# AMU-S04-V00-Microcontroller.net
KiCad netlist of a schematic drawn in Altium Designer
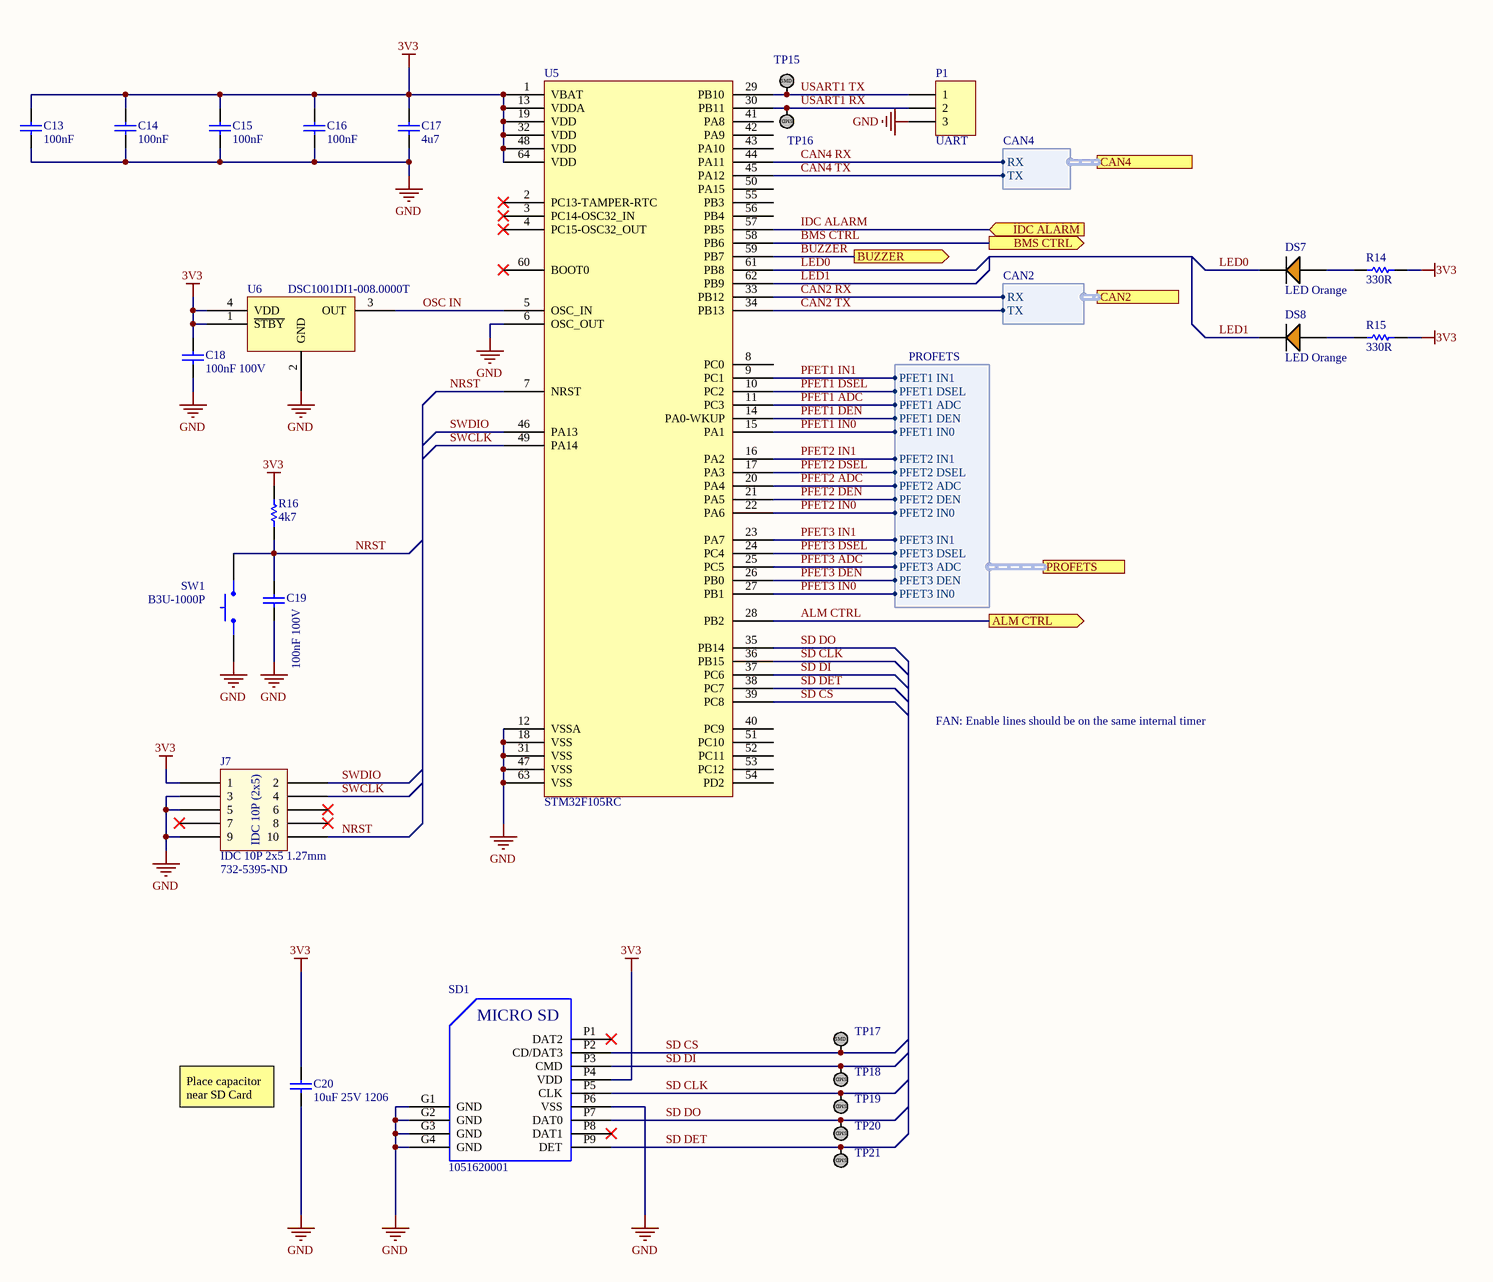
[diagram p0: AMU-S04-V00-Microcontroller.SchDoc]

(export (version "E")
  (design (tool "Eeschema 10.0.6"))
  (components
    (comp (ref "C13")
      (value "100nF")
      (footprint "Cap_Ceramic_0603")
      (description "Capacitor, Ceramic, SMD, 100nF, 50V, 5%, X7R, 0603")
      (libsource (lib "StandardCapacitors") (part "100nF 50V 5% X7R 0603"))
    )
    (comp (ref "C14")
      (value "100nF")
      (footprint "Cap_Ceramic_0603")
      (description "Capacitor, Ceramic, SMD, 100nF, 50V, 5%, X7R, 0603")
      (libsource (lib "StandardCapacitors") (part "100nF 50V 5% X7R 0603"))
    )
    (comp (ref "C15")
      (value "100nF")
      (footprint "Cap_Ceramic_0603")
      (description "Capacitor, Ceramic, SMD, 100nF, 50V, 5%, X7R, 0603")
      (libsource (lib "StandardCapacitors") (part "100nF 50V 5% X7R 0603"))
    )
    (comp (ref "C16")
      (value "100nF")
      (footprint "Cap_Ceramic_0603")
      (description "Capacitor, Ceramic, SMD, 100nF, 50V, 5%, X7R, 0603")
      (libsource (lib "StandardCapacitors") (part "100nF 50V 5% X7R 0603"))
    )
    (comp (ref "C17")
      (value "4u7")
      (footprint "Cap_Ceramic_0603")
      (description "Capacitor, Ceramic, SMD, 4u7, 50V, 5%, X7R, 0603")
      (libsource (lib "StandardCapacitors") (part "4u7 50V 5% X7R 0603"))
    )
    (comp (ref "C18")
      (value "100nF 100V")
      (footprint "Cap_Ceramic_0603")
      (description "Capacitor, Ceramic, SMD, 100nF, 100V, 5%, X7R, 0603")
      (libsource (lib "StandardCapacitors") (part "100nF 100V 5% X7R 0603"))
    )
    (comp (ref "C19")
      (value "100nF 100V")
      (footprint "Cap_Ceramic_0603")
      (description "Capacitor, Ceramic, SMD, 100nF, 100V, 5%, X7R, 0603")
      (libsource (lib "StandardCapacitors") (part "100nF 100V 5% X7R 0603"))
    )
    (comp (ref "C20")
      (value "10uF 25V 1206")
      (footprint "Cap_Ceramic_1206")
      (description "Capacitor, Ceramic, SMD, 10uF, 25V, 10%, X7R, 1206")
      (libsource (lib "StandardCapacitors") (part "10uF 25V 10% X7R 1206"))
    )
    (comp (ref "DS7")
      (value "LED Orange")
      (footprint "LED ORANGE 0603")
      (libsource (lib "QUTMS_LEDLibrary") (part "LED ORANGE 0603"))
    )
    (comp (ref "DS8")
      (value "LED Orange")
      (footprint "LED ORANGE 0603")
      (libsource (lib "QUTMS_LEDLibrary") (part "LED ORANGE 0603"))
    )
    (comp (ref "J7")
      (value "IDC 10P 2x5 1.27mm")
      (footprint "IDC 1.27MM 10P")
      (libsource (lib "IDCConnectors") (part "IDC 10P 2x5 1.27mm"))
    )
    (comp (ref "P1")
      (value "UART")
      (footprint "HDR1X3")
      (description "Header, 3-Pin")
      (fields (field (name "PUBLISHER") "Altium Limited"))
      (libsource (lib "Miscellaneous Connectors") (part "Header 3"))
    )
    (comp (ref "R14")
      (value "330R")
      (footprint "Res_ThinFilm_0603")
      (description "Resistor, SMD, 330R, 0.1W, 5%, 0603")
      (libsource (lib "StandardResistors") (part "330R 5% 0603"))
    )
    (comp (ref "R15")
      (value "330R")
      (footprint "Res_ThinFilm_0603")
      (description "Resistor, SMD, 330R, 0.1W, 5%, 0603")
      (libsource (lib "StandardResistors") (part "330R 5% 0603"))
    )
    (comp (ref "R16")
      (value "4k7")
      (footprint "Res_ThinFilm_0603")
      (description "Resistor, SMD, 4k7, 0.1W, 5%, 0603")
      (libsource (lib "StandardResistors") (part "4k7 5% 0603"))
    )
    (comp (ref "SD1")
      (value "1051620001")
      (footprint "1051620001")
      (description "9 (8 + 1) Position Card Connector microSD™ Surface Mount, Right Angle Gold")
      (libsource (lib "QUTMS_SDLibrary") (part "1051620001"))
    )
    (comp (ref "SW1")
      (value "B3U-1000P")
      (footprint "BTN B3U-1000P")
      (description "Omron B3U-1000P Ultra Miniture Switch")
      (libsource (lib "QUTMS_SwitchLibrary") (part "BTN B3U-1000P"))
    )
    (comp (ref "TP15")
      (value "TestPoint_SMD")
      (footprint "TestPointSMD")
      (libsource (lib "StandardTest") (part "TestPoint_SMD"))
    )
    (comp (ref "TP16")
      (value "TestPoint_SMD")
      (footprint "TestPointSMD")
      (libsource (lib "StandardTest") (part "TestPoint_SMD"))
    )
    (comp (ref "TP17")
      (value "TestPoint_SMD")
      (footprint "TestPointSMD")
      (libsource (lib "StandardTest") (part "TestPoint_SMD"))
    )
    (comp (ref "TP18")
      (value "TestPoint_SMD")
      (footprint "TestPointSMD")
      (libsource (lib "StandardTest") (part "TestPoint_SMD"))
    )
    (comp (ref "TP19")
      (value "TestPoint_SMD")
      (footprint "TestPointSMD")
      (libsource (lib "StandardTest") (part "TestPoint_SMD"))
    )
    (comp (ref "TP20")
      (value "TestPoint_SMD")
      (footprint "TestPointSMD")
      (libsource (lib "StandardTest") (part "TestPoint_SMD"))
    )
    (comp (ref "TP21")
      (value "TestPoint_SMD")
      (footprint "TestPointSMD")
      (libsource (lib "StandardTest") (part "TestPoint_SMD"))
    )
    (comp (ref "U5")
      (value "STM32F105RC")
      (footprint "STM32F105RC")
      (description "ARM® Cortex®-M3 STM32F1 Microcontroller IC 32-Bit 72MHz 256KB (256K x 8) FLASH 64-LQFP (10x10)")
      (libsource (lib "QUTMS_STM32Library") (part "STM32F105RC"))
    )
    (comp (ref "U6")
      (value "DSC1001DI1-008.0000T")
      (footprint "DSC1001DI1-008.0000TCT-ND")
      (description "on 8MHz XO (Standard) CMOS Oscillator 1.8 ~ 3.3V Standby (Power Down) 4-SMD, No Lead")
      (libsource (lib "QUTMS_CrystalLibrary") (part "DSC1001DI1-008.0000T"))
    )
  )
  (nets
    (net (code "4") (name "/ALM CTRL") (class "Default")
      (node (ref "U5") (pin "28") (pinfunction "PB2_28") (pintype "passive"))
    )
    (net (code "5") (name "/BMS CTRL") (class "Default")
      (node (ref "U5") (pin "58") (pinfunction "PB6_58") (pintype "passive"))
    )
    (net (code "6") (name "/BUZZER") (class "Default")
      (node (ref "U5") (pin "59") (pinfunction "PB7_59") (pintype "passive"))
    )
    (net (code "7") (name "/CAN2 RX") (class "Default")
      (node (ref "U5") (pin "33") (pinfunction "PB12_33") (pintype "passive"))
    )
    (net (code "8") (name "/CAN2 TX") (class "Default")
      (node (ref "U5") (pin "34") (pinfunction "PB13_34") (pintype "passive"))
    )
    (net (code "9") (name "/CAN4 RX") (class "Default")
      (node (ref "U5") (pin "44") (pinfunction "PA11_44") (pintype "passive"))
    )
    (net (code "10") (name "/CAN4 TX") (class "Default")
      (node (ref "U5") (pin "45") (pinfunction "PA12_45") (pintype "passive"))
    )
    (net (code "11") (name "/IDC ALARM") (class "Default")
      (node (ref "U5") (pin "57") (pinfunction "PB5_57") (pintype "passive"))
    )
    (net (code "12") (name "/LED0") (class "Default")
      (node (ref "DS7") (pin "2") (pinfunction "C_2") (pintype "passive"))
      (node (ref "U5") (pin "61") (pinfunction "PB8_61") (pintype "passive"))
    )
    (net (code "13") (name "/LED1") (class "Default")
      (node (ref "DS8") (pin "2") (pinfunction "C_2") (pintype "passive"))
      (node (ref "U5") (pin "62") (pinfunction "PB9_62") (pintype "passive"))
    )
    (net (code "14") (name "/NRST") (class "Default")
      (node (ref "C19") (pin "2") (pinfunction "2_2") (pintype "passive"))
      (node (ref "J7") (pin "10") (pinfunction "10_10") (pintype "passive"))
      (node (ref "R16") (pin "1") (pinfunction "1_1") (pintype "passive"))
      (node (ref "SW1") (pin "2") (pinfunction "2_2") (pintype "passive"))
      (node (ref "U5") (pin "7") (pinfunction "NRST_7") (pintype "passive"))
    )
    (net (code "15") (name "/OSC IN") (class "Default")
      (node (ref "U5") (pin "5") (pinfunction "OSC_IN_5") (pintype "passive"))
      (node (ref "U6") (pin "3") (pinfunction "OUT_3") (pintype "passive"))
    )
    (net (code "16") (name "/PFET1 ADC") (class "Default")
      (node (ref "U5") (pin "11") (pinfunction "PC3_11") (pintype "passive"))
    )
    (net (code "17") (name "/PFET1 DEN") (class "Default")
      (node (ref "U5") (pin "14") (pinfunction "PA0-WKUP_14") (pintype "passive"))
    )
    (net (code "18") (name "/PFET1 DSEL") (class "Default")
      (node (ref "U5") (pin "10") (pinfunction "PC2_10") (pintype "passive"))
    )
    (net (code "19") (name "/PFET1 IN0") (class "Default")
      (node (ref "U5") (pin "15") (pinfunction "PA1_15") (pintype "passive"))
    )
    (net (code "20") (name "/PFET1 IN1") (class "Default")
      (node (ref "U5") (pin "9") (pinfunction "PC1_9") (pintype "passive"))
    )
    (net (code "21") (name "/PFET2 ADC") (class "Default")
      (node (ref "U5") (pin "20") (pinfunction "PA4_20") (pintype "passive"))
    )
    (net (code "22") (name "/PFET2 DEN") (class "Default")
      (node (ref "U5") (pin "21") (pinfunction "PA5_21") (pintype "passive"))
    )
    (net (code "23") (name "/PFET2 DSEL") (class "Default")
      (node (ref "U5") (pin "17") (pinfunction "PA3_17") (pintype "passive"))
    )
    (net (code "24") (name "/PFET2 IN0") (class "Default")
      (node (ref "U5") (pin "22") (pinfunction "PA6_22") (pintype "passive"))
    )
    (net (code "25") (name "/PFET2 IN1") (class "Default")
      (node (ref "U5") (pin "16") (pinfunction "PA2_16") (pintype "passive"))
    )
    (net (code "26") (name "/PFET3 ADC") (class "Default")
      (node (ref "U5") (pin "25") (pinfunction "PC5_25") (pintype "passive"))
    )
    (net (code "27") (name "/PFET3 DEN") (class "Default")
      (node (ref "U5") (pin "26") (pinfunction "PB0_26") (pintype "passive"))
    )
    (net (code "28") (name "/PFET3 DSEL") (class "Default")
      (node (ref "U5") (pin "24") (pinfunction "PC4_24") (pintype "passive"))
    )
    (net (code "29") (name "/PFET3 IN0") (class "Default")
      (node (ref "U5") (pin "27") (pinfunction "PB1_27") (pintype "passive"))
    )
    (net (code "30") (name "/PFET3 IN1") (class "Default")
      (node (ref "U5") (pin "23") (pinfunction "PA7_23") (pintype "passive"))
    )
    (net (code "31") (name "/SD CLK") (class "Default")
      (node (ref "SD1") (pin "P5") (pinfunction "CLK_P5") (pintype "passive"))
      (node (ref "TP19") (pin "1") (pinfunction "1_1") (pintype "passive"))
      (node (ref "U5") (pin "36") (pinfunction "PB15_36") (pintype "passive"))
    )
    (net (code "32") (name "/SD CS") (class "Default")
      (node (ref "SD1") (pin "P2") (pinfunction "CD/DAT3_P2") (pintype "passive"))
      (node (ref "TP17") (pin "1") (pinfunction "1_1") (pintype "passive"))
      (node (ref "U5") (pin "39") (pinfunction "PC8_39") (pintype "passive"))
    )
    (net (code "33") (name "/SD DET") (class "Default")
      (node (ref "SD1") (pin "P9") (pinfunction "DET_P9") (pintype "passive"))
      (node (ref "TP21") (pin "1") (pinfunction "1_1") (pintype "passive"))
      (node (ref "U5") (pin "38") (pinfunction "PC7_38") (pintype "passive"))
    )
    (net (code "34") (name "/SD DI") (class "Default")
      (node (ref "SD1") (pin "P3") (pinfunction "CMD_P3") (pintype "passive"))
      (node (ref "TP18") (pin "1") (pinfunction "1_1") (pintype "passive"))
      (node (ref "U5") (pin "37") (pinfunction "PC6_37") (pintype "passive"))
    )
    (net (code "35") (name "/SD DO") (class "Default")
      (node (ref "SD1") (pin "P7") (pinfunction "DAT0_P7") (pintype "passive"))
      (node (ref "TP20") (pin "1") (pinfunction "1_1") (pintype "passive"))
      (node (ref "U5") (pin "35") (pinfunction "PB14_35") (pintype "passive"))
    )
    (net (code "36") (name "/SWCLK") (class "Default")
      (node (ref "J7") (pin "4") (pinfunction "4_4") (pintype "passive"))
      (node (ref "U5") (pin "49") (pinfunction "PA14_49") (pintype "passive"))
    )
    (net (code "37") (name "/SWDIO") (class "Default")
      (node (ref "J7") (pin "2") (pinfunction "2_2") (pintype "passive"))
      (node (ref "U5") (pin "46") (pinfunction "PA13_46") (pintype "passive"))
    )
    (net (code "38") (name "/USART1 RX") (class "Default")
      (node (ref "P1") (pin "2") (pinfunction "2_2") (pintype "passive"))
      (node (ref "TP16") (pin "1") (pinfunction "1_1") (pintype "passive"))
      (node (ref "U5") (pin "30") (pinfunction "PB11_30") (pintype "passive"))
    )
    (net (code "39") (name "/USART1 TX") (class "Default")
      (node (ref "P1") (pin "1") (pinfunction "1_1") (pintype "passive"))
      (node (ref "TP15") (pin "1") (pinfunction "1_1") (pintype "passive"))
      (node (ref "U5") (pin "29") (pinfunction "PB10_29") (pintype "passive"))
    )
    (net (code "43") (name "3V3") (class "Default")
      (node (ref "C13") (pin "2") (pinfunction "2_2") (pintype "passive"))
      (node (ref "C14") (pin "2") (pinfunction "2_2") (pintype "passive"))
      (node (ref "C15") (pin "2") (pinfunction "2_2") (pintype "passive"))
      (node (ref "C16") (pin "2") (pinfunction "2_2") (pintype "passive"))
      (node (ref "C17") (pin "2") (pinfunction "2_2") (pintype "passive"))
      (node (ref "C18") (pin "2") (pinfunction "2_2") (pintype "passive"))
      (node (ref "C20") (pin "2") (pinfunction "2_2") (pintype "passive"))
      (node (ref "J7") (pin "1") (pinfunction "1_1") (pintype "passive"))
      (node (ref "R14") (pin "2") (pinfunction "2_2") (pintype "passive"))
      (node (ref "R15") (pin "2") (pinfunction "2_2") (pintype "passive"))
      (node (ref "R16") (pin "2") (pinfunction "2_2") (pintype "passive"))
      (node (ref "SD1") (pin "P4") (pinfunction "VDD_P4") (pintype "passive"))
      (node (ref "U5") (pin "1") (pinfunction "VBAT_1") (pintype "passive"))
      (node (ref "U5") (pin "13") (pinfunction "VDDA_13") (pintype "passive"))
      (node (ref "U5") (pin "19") (pinfunction "VDD_19") (pintype "passive"))
      (node (ref "U5") (pin "32") (pinfunction "VDD_32") (pintype "passive"))
      (node (ref "U5") (pin "48") (pinfunction "VDD_48") (pintype "passive"))
      (node (ref "U5") (pin "64") (pinfunction "VDD_64") (pintype "passive"))
      (node (ref "U6") (pin "1") (pinfunction "~{STBY}_1") (pintype "passive"))
      (node (ref "U6") (pin "4") (pinfunction "VDD_4") (pintype "passive"))
    )
    (net (code "44") (name "GND") (class "Default")
      (node (ref "C13") (pin "1") (pinfunction "1_1") (pintype "passive"))
      (node (ref "C14") (pin "1") (pinfunction "1_1") (pintype "passive"))
      (node (ref "C15") (pin "1") (pinfunction "1_1") (pintype "passive"))
      (node (ref "C16") (pin "1") (pinfunction "1_1") (pintype "passive"))
      (node (ref "C17") (pin "1") (pinfunction "1_1") (pintype "passive"))
      (node (ref "C18") (pin "1") (pinfunction "1_1") (pintype "passive"))
      (node (ref "C19") (pin "1") (pinfunction "1_1") (pintype "passive"))
      (node (ref "C20") (pin "1") (pinfunction "1_1") (pintype "passive"))
      (node (ref "J7") (pin "3") (pinfunction "3_3") (pintype "passive"))
      (node (ref "J7") (pin "5") (pinfunction "5_5") (pintype "passive"))
      (node (ref "J7") (pin "9") (pinfunction "9_9") (pintype "passive"))
      (node (ref "P1") (pin "3") (pinfunction "3_3") (pintype "passive"))
      (node (ref "SD1") (pin "G1") (pinfunction "GND_G1") (pintype "passive"))
      (node (ref "SD1") (pin "G2") (pinfunction "GND_G2") (pintype "passive"))
      (node (ref "SD1") (pin "G3") (pinfunction "GND_G3") (pintype "passive"))
      (node (ref "SD1") (pin "G4") (pinfunction "GND_G4") (pintype "passive"))
      (node (ref "SD1") (pin "P6") (pinfunction "VSS_P6") (pintype "passive"))
      (node (ref "SW1") (pin "1") (pinfunction "1_1") (pintype "passive"))
      (node (ref "U5") (pin "12") (pinfunction "VSSA_12") (pintype "passive"))
      (node (ref "U5") (pin "18") (pinfunction "VSS_18") (pintype "passive"))
      (node (ref "U5") (pin "31") (pinfunction "VSS_31") (pintype "passive"))
      (node (ref "U5") (pin "47") (pinfunction "VSS_47") (pintype "passive"))
      (node (ref "U5") (pin "6") (pinfunction "OSC_OUT_6") (pintype "passive"))
      (node (ref "U5") (pin "63") (pinfunction "VSS_63") (pintype "passive"))
      (node (ref "U6") (pin "2") (pinfunction "GND_2") (pintype "passive"))
    )
    (net (code "45") (name "Net-(DS7-A)") (class "Default")
      (node (ref "DS7") (pin "1") (pinfunction "A_1") (pintype "passive"))
      (node (ref "R14") (pin "1") (pinfunction "1_1") (pintype "passive"))
    )
    (net (code "46") (name "Net-(DS8-A)") (class "Default")
      (node (ref "DS8") (pin "1") (pinfunction "A_1") (pintype "passive"))
      (node (ref "R15") (pin "1") (pinfunction "1_1") (pintype "passive"))
    )
    (net (code "47") (name "unconnected-(J7-Pad6)") (class "Default")
      (node (ref "J7") (pin "6") (pinfunction "6_6") (pintype "passive+no_connect"))
    )
    (net (code "48") (name "unconnected-(J7-Pad7)") (class "Default")
      (node (ref "J7") (pin "7") (pinfunction "7_7") (pintype "passive+no_connect"))
    )
    (net (code "49") (name "unconnected-(J7-Pad8)") (class "Default")
      (node (ref "J7") (pin "8") (pinfunction "8_8") (pintype "passive+no_connect"))
    )
    (net (code "50") (name "unconnected-(SD1-DAT1-PadP8)") (class "Default")
      (node (ref "SD1") (pin "P8") (pinfunction "DAT1_P8") (pintype "passive+no_connect"))
    )
    (net (code "51") (name "unconnected-(SD1-DAT2-PadP1)") (class "Default")
      (node (ref "SD1") (pin "P1") (pinfunction "DAT2_P1") (pintype "passive+no_connect"))
    )
    (net (code "52") (name "unconnected-(U5-BOOT0-Pad60)") (class "Default")
      (node (ref "U5") (pin "60") (pinfunction "BOOT0_60") (pintype "passive+no_connect"))
    )
    (net (code "53") (name "unconnected-(U5-PA8-Pad41)") (class "Default")
      (node (ref "U5") (pin "41") (pinfunction "PA8_41") (pintype "passive"))
    )
    (net (code "54") (name "unconnected-(U5-PA9-Pad42)") (class "Default")
      (node (ref "U5") (pin "42") (pinfunction "PA9_42") (pintype "passive"))
    )
    (net (code "55") (name "unconnected-(U5-PA10-Pad43)") (class "Default")
      (node (ref "U5") (pin "43") (pinfunction "PA10_43") (pintype "passive"))
    )
    (net (code "56") (name "unconnected-(U5-PA15-Pad50)") (class "Default")
      (node (ref "U5") (pin "50") (pinfunction "PA15_50") (pintype "passive"))
    )
    (net (code "57") (name "unconnected-(U5-PB3-Pad55)") (class "Default")
      (node (ref "U5") (pin "55") (pinfunction "PB3_55") (pintype "passive"))
    )
    (net (code "58") (name "unconnected-(U5-PB4-Pad56)") (class "Default")
      (node (ref "U5") (pin "56") (pinfunction "PB4_56") (pintype "passive"))
    )
    (net (code "59") (name "unconnected-(U5-PC0-Pad8)") (class "Default")
      (node (ref "U5") (pin "8") (pinfunction "PC0_8") (pintype "passive"))
    )
    (net (code "60") (name "unconnected-(U5-PC9-Pad40)") (class "Default")
      (node (ref "U5") (pin "40") (pinfunction "PC9_40") (pintype "passive"))
    )
    (net (code "61") (name "unconnected-(U5-PC10-Pad51)") (class "Default")
      (node (ref "U5") (pin "51") (pinfunction "PC10_51") (pintype "passive"))
    )
    (net (code "62") (name "unconnected-(U5-PC11-Pad52)") (class "Default")
      (node (ref "U5") (pin "52") (pinfunction "PC11_52") (pintype "passive"))
    )
    (net (code "63") (name "unconnected-(U5-PC12-Pad53)") (class "Default")
      (node (ref "U5") (pin "53") (pinfunction "PC12_53") (pintype "passive"))
    )
    (net (code "64") (name "unconnected-(U5-PC13-TAMPER-RTC-Pad2)") (class "Default")
      (node (ref "U5") (pin "2") (pinfunction "PC13-TAMPER-RTC_2") (pintype "passive+no_connect"))
    )
    (net (code "65") (name "unconnected-(U5-PC14-OSC32_IN-Pad3)") (class "Default")
      (node (ref "U5") (pin "3") (pinfunction "PC14-OSC32_IN_3") (pintype "passive+no_connect"))
    )
    (net (code "66") (name "unconnected-(U5-PC15-OSC32_OUT-Pad4)") (class "Default")
      (node (ref "U5") (pin "4") (pinfunction "PC15-OSC32_OUT_4") (pintype "passive+no_connect"))
    )
    (net (code "67") (name "unconnected-(U5-PD2-Pad54)") (class "Default")
      (node (ref "U5") (pin "54") (pinfunction "PD2_54") (pintype "passive"))
    )
  )
)
